# PROC010C_Tempsensor.net
KiCad netlist of a schematic drawn in Altium Designer
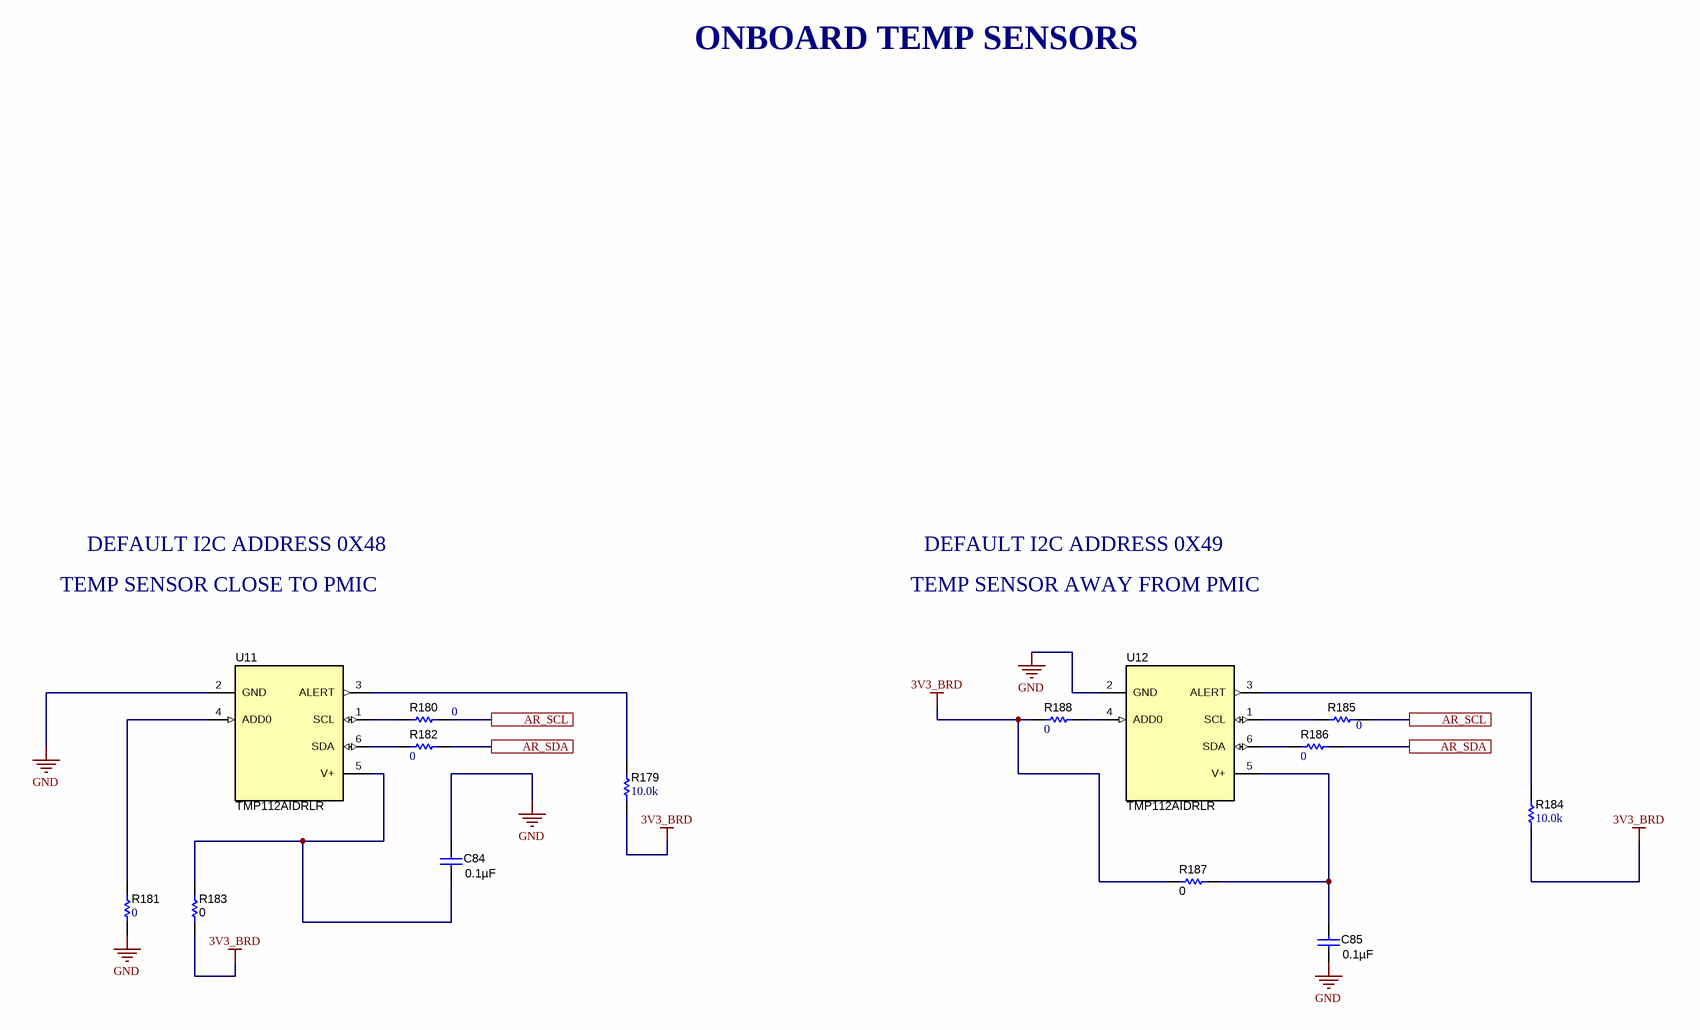
[diagram p0: PROC010C_Tempsensor.SchDoc]

(export (version "E")
  (design (tool "Eeschema 10.0.6"))
  (components
    (comp (ref "C84")
      (value "C0402C104K8RACTU")
      (footprint "0402L")
      (description "CAP, CERM, 0.1 µF, 10 V,+/- 10%, X7R, 0402")
      (fields (field (name "MANUFACTURER") "Kemet") (field (name "VALUEDISPLAYED") "0.1µF"))
      (libsource (lib "Altium Vault - TI") (part "Capacitor"))
    )
    (comp (ref "C85")
      (value "C0402C104K8RACTU")
      (footprint "0402L")
      (description "CAP, CERM, 0.1 µF, 10 V,+/- 10%, X7R, 0402")
      (fields (field (name "MANUFACTURER") "Kemet") (field (name "VALUEDISPLAYED") "0.1µF"))
      (libsource (lib "Altium Vault - TI") (part "Capacitor"))
    )
    (comp (ref "R179")
      (value "CRCW040210K0FKED")
      (footprint "0402L")
      (description "RES, 10.0 k, 1%, 0.063 W, AEC-Q200 Grade 0, 0402")
      (fields (field (name "MANUFACTURER") "Vishay-Dale") (field (name "VALUEDISPLAYED") "10.0k"))
      (libsource (lib "Altium Vault - TI") (part "Resistor"))
    )
    (comp (ref "R180")
      (value "CRCW02010000Z0ED")
      (footprint "0201_Silk")
      (description "RES, 0, 5%, 0.05 W, 0201")
      (fields (field (name "MANUFACTURER") "Vishay-Dale") (field (name "VALUEDISPLAYED") "0"))
      (libsource (lib "Altium Vault - TI") (part "Resistor"))
    )
    (comp (ref "R181")
      (value "CRCW02010000Z0ED")
      (footprint "0201_Silk")
      (description "RES, 0, 5%, 0.05 W, 0201")
      (fields (field (name "MANUFACTURER") "Vishay-Dale") (field (name "VALUEDISPLAYED") "0"))
      (libsource (lib "Altium Vault - TI") (part "Resistor"))
    )
    (comp (ref "R182")
      (value "CRCW02010000Z0ED")
      (footprint "0201_Silk")
      (description "RES, 0, 5%, 0.05 W, 0201")
      (fields (field (name "MANUFACTURER") "Vishay-Dale") (field (name "VALUEDISPLAYED") "0"))
      (libsource (lib "Altium Vault - TI") (part "Resistor"))
    )
    (comp (ref "R183")
      (value "ERJ-2GE0R00X")
      (footprint "0402L")
      (description "RES, 0, 5%, 0.063 W, 0402")
      (fields
        (field (name "MANUFACTURER") "Panasonic")
        (field (name "VALUEDISPLAYED") "0")
        (field (name "PUBLISHER") "Texas Instruments")
      )
      (libsource (lib "Altium Vault - TI") (part "Resistor"))
    )
    (comp (ref "R184")
      (value "CRCW040210K0FKED")
      (footprint "0402L")
      (description "RES, 10.0 k, 1%, 0.063 W, AEC-Q200 Grade 0, 0402")
      (fields (field (name "MANUFACTURER") "Vishay-Dale") (field (name "VALUEDISPLAYED") "10.0k"))
      (libsource (lib "Altium Vault - TI") (part "Resistor"))
    )
    (comp (ref "R185")
      (value "CRCW02010000Z0ED")
      (footprint "0201_Silk")
      (description "RES, 0, 5%, 0.05 W, 0201")
      (fields (field (name "MANUFACTURER") "Vishay-Dale") (field (name "VALUEDISPLAYED") "0"))
      (libsource (lib "Altium Vault - TI") (part "Resistor"))
    )
    (comp (ref "R186")
      (value "CRCW02010000Z0ED")
      (footprint "0201_Silk")
      (description "RES, 0, 5%, 0.05 W, 0201")
      (fields (field (name "MANUFACTURER") "Vishay-Dale") (field (name "VALUEDISPLAYED") "0"))
      (libsource (lib "Altium Vault - TI") (part "Resistor"))
    )
    (comp (ref "R187")
      (value "ERJ-2GE0R00X")
      (footprint "0402L")
      (description "RES, 0, 5%, 0.063 W, 0402")
      (fields
        (field (name "MANUFACTURER") "Panasonic")
        (field (name "VALUEDISPLAYED") "0")
        (field (name "PUBLISHER") "Texas Instruments")
      )
      (libsource (lib "Altium Vault - TI") (part "Resistor"))
    )
    (comp (ref "R188")
      (value "CRCW02010000Z0ED")
      (footprint "0201_Silk")
      (description "RES, 0, 5%, 0.05 W, 0201")
      (fields (field (name "MANUFACTURER") "Vishay-Dale") (field (name "VALUEDISPLAYED") "0"))
      (libsource (lib "Altium Vault - TI") (part "Resistor"))
    )
    (comp (ref "U11")
      (value "TMP112AIDRLR")
      (footprint "DRL0006A")
      (fields
        (field (name "ALTERNATE PARTNUMBER") "TMP112AIDRLT")
        (field (name "MANUFACTURER") "Texas Instruments")
        (field (name "PARTNUMBER") "TMP112AIDRLR")
        (field (name "PUBLISHER") "Texas Instruments")
      )
      (libsource (lib "Altium Vault - TI") (part "TMP112"))
    )
    (comp (ref "U12")
      (value "TMP112AIDRLR")
      (footprint "DRL0006A")
      (fields
        (field (name "ALTERNATE PARTNUMBER") "TMP112AIDRLT")
        (field (name "MANUFACTURER") "Texas Instruments")
        (field (name "PARTNUMBER") "TMP112AIDRLR")
        (field (name "PUBLISHER") "Texas Instruments")
      )
      (libsource (lib "Altium Vault - TI") (part "CMP-0067397-2"))
    )
  )
  (nets
    (net (code "1") (name "/AR_SCL") (class "Default")
      (node (ref "R180") (pin "1") (pinfunction "1_1") (pintype "passive"))
      (node (ref "R185") (pin "1") (pinfunction "1_1") (pintype "passive"))
    )
    (net (code "2") (name "/AR_SDA") (class "Default")
      (node (ref "R182") (pin "2") (pinfunction "2_2") (pintype "passive"))
      (node (ref "R186") (pin "2") (pinfunction "2_2") (pintype "passive"))
    )
    (net (code "3") (name "3V3_BRD") (class "Default")
      (node (ref "R179") (pin "2") (pinfunction "2_2") (pintype "passive"))
      (node (ref "R183") (pin "2") (pinfunction "2_2") (pintype "passive"))
      (node (ref "R184") (pin "2") (pinfunction "2_2") (pintype "passive"))
      (node (ref "R187") (pin "2") (pinfunction "2_2") (pintype "passive"))
      (node (ref "R188") (pin "1") (pinfunction "1_1") (pintype "passive"))
    )
    (net (code "4") (name "GND") (class "Default")
      (node (ref "C84") (pin "1") (pinfunction "1_1") (pintype "passive"))
      (node (ref "C85") (pin "2") (pinfunction "2_2") (pintype "passive"))
      (node (ref "R181") (pin "2") (pinfunction "2_2") (pintype "passive"))
      (node (ref "U11") (pin "2") (pinfunction "GND_2") (pintype "power_in"))
      (node (ref "U12") (pin "2") (pinfunction "GND_2") (pintype "power_in"))
    )
    (net (code "5") (name "Net-(U11-ADD0)") (class "Default")
      (node (ref "R181") (pin "1") (pinfunction "1_1") (pintype "passive"))
      (node (ref "U11") (pin "4") (pinfunction "ADD0_4") (pintype "input"))
    )
    (net (code "6") (name "Net-(U11-ALERT)") (class "Default")
      (node (ref "R179") (pin "1") (pinfunction "1_1") (pintype "passive"))
      (node (ref "U11") (pin "3") (pinfunction "ALERT_3") (pintype "output"))
    )
    (net (code "7") (name "Net-(U11-SCL)") (class "Default")
      (node (ref "R180") (pin "2") (pinfunction "2_2") (pintype "passive"))
      (node (ref "U11") (pin "1") (pinfunction "SCL_1") (pintype "bidirectional"))
    )
    (net (code "8") (name "Net-(U11-SDA)") (class "Default")
      (node (ref "R182") (pin "1") (pinfunction "1_1") (pintype "passive"))
      (node (ref "U11") (pin "6") (pinfunction "SDA_6") (pintype "bidirectional"))
    )
    (net (code "9") (name "Net-(U11-V+)") (class "Default")
      (node (ref "C84") (pin "2") (pinfunction "2_2") (pintype "passive"))
      (node (ref "R183") (pin "1") (pinfunction "1_1") (pintype "passive"))
      (node (ref "U11") (pin "5") (pinfunction "V+_5") (pintype "power_in"))
    )
    (net (code "10") (name "Net-(U12-ADD0)") (class "Default")
      (node (ref "R188") (pin "2") (pinfunction "2_2") (pintype "passive"))
      (node (ref "U12") (pin "4") (pinfunction "ADD0_4") (pintype "input"))
    )
    (net (code "11") (name "Net-(U12-ALERT)") (class "Default")
      (node (ref "R184") (pin "1") (pinfunction "1_1") (pintype "passive"))
      (node (ref "U12") (pin "3") (pinfunction "ALERT_3") (pintype "output"))
    )
    (net (code "12") (name "Net-(U12-SCL)") (class "Default")
      (node (ref "R185") (pin "2") (pinfunction "2_2") (pintype "passive"))
      (node (ref "U12") (pin "1") (pinfunction "SCL_1") (pintype "bidirectional"))
    )
    (net (code "13") (name "Net-(U12-SDA)") (class "Default")
      (node (ref "R186") (pin "1") (pinfunction "1_1") (pintype "passive"))
      (node (ref "U12") (pin "6") (pinfunction "SDA_6") (pintype "bidirectional"))
    )
    (net (code "14") (name "Net-(U12-V+)") (class "Default")
      (node (ref "C85") (pin "1") (pinfunction "1_1") (pintype "passive"))
      (node (ref "R187") (pin "1") (pinfunction "1_1") (pintype "passive"))
      (node (ref "U12") (pin "5") (pinfunction "V+_5") (pintype "power_in"))
    )
  )
)
